# Lights.net
KiCad netlist of a schematic drawn in Altium Designer
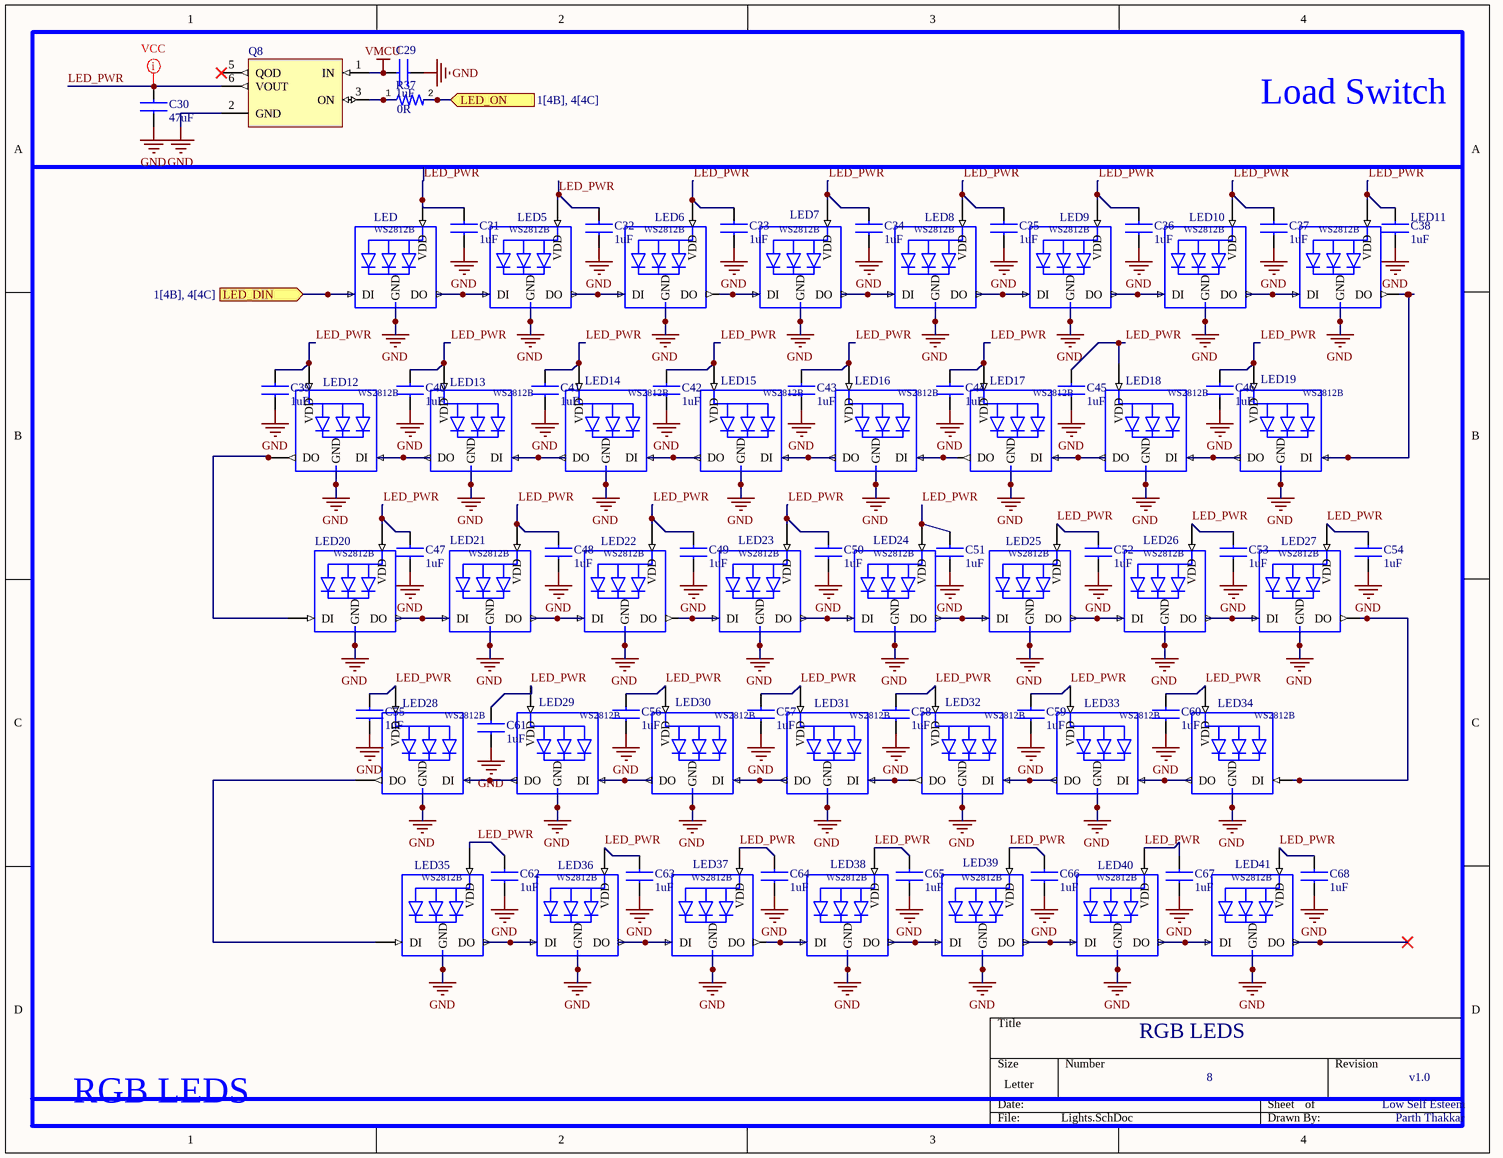
[diagram p0:  Lights.SchDoc]

(export (version "E")
  (design (tool "Eeschema 10.0.6"))
  (components
    (comp (ref "C29")
      (value "1uF")
      (footprint "Capacitor 0603")
      (fields
        (field (name "MANUFACTURER") "Murata")
        (field (name "MANUFACTURER PART NUMBER") "GRM188R61A105KA61D")
        (field (name "Comment") "CAP 1uF 10V 0603")
      )
      (libsource (lib "Keyboard_parts") (part "CAP 1uF 10V 0603"))
    )
    (comp (ref "C30")
      (value "47uF")
      (footprint "CAPACITOR 0805")
      (description "Multilayer Ceramic Capacitors MLCC - SMD/SMT 0805 47uF 10volts *Derate Voltage/Temp")
      (fields
        (field (name "MANUFACTURER") "Murata")
        (field (name "MANUFACTURER PART NUMBER") "GRM21BR61A476ME15K")
      )
      (libsource (lib "Keyboard_parts") (part "CAP 47uF 10V 0805"))
    )
    (comp (ref "C31")
      (value "1uF")
      (footprint "Capacitor 0603")
      (fields
        (field (name "MANUFACTURER") "Murata")
        (field (name "MANUFACTURER PART NUMBER") "GRM188R61A105KA61D")
        (field (name "Comment") "CAP 1uF 10V 0603")
      )
      (libsource (lib "Keyboard_parts") (part "CAP 1uF 10V 0603"))
    )
    (comp (ref "C32")
      (value "1uF")
      (footprint "Capacitor 0603")
      (fields
        (field (name "MANUFACTURER") "Murata")
        (field (name "MANUFACTURER PART NUMBER") "GRM188R61A105KA61D")
        (field (name "Comment") "CAP 1uF 10V 0603")
      )
      (libsource (lib "Keyboard_parts") (part "CAP 1uF 10V 0603"))
    )
    (comp (ref "C33")
      (value "1uF")
      (footprint "Capacitor 0603")
      (fields
        (field (name "MANUFACTURER") "Murata")
        (field (name "MANUFACTURER PART NUMBER") "GRM188R61A105KA61D")
        (field (name "Comment") "CAP 1uF 10V 0603")
      )
      (libsource (lib "Keyboard_parts") (part "CAP 1uF 10V 0603"))
    )
    (comp (ref "C34")
      (value "1uF")
      (footprint "Capacitor 0603")
      (fields
        (field (name "MANUFACTURER") "Murata")
        (field (name "MANUFACTURER PART NUMBER") "GRM188R61A105KA61D")
        (field (name "Comment") "CAP 1uF 10V 0603")
      )
      (libsource (lib "Keyboard_parts") (part "CAP 1uF 10V 0603"))
    )
    (comp (ref "C35")
      (value "1uF")
      (footprint "Capacitor 0603")
      (fields
        (field (name "MANUFACTURER") "Murata")
        (field (name "MANUFACTURER PART NUMBER") "GRM188R61A105KA61D")
        (field (name "Comment") "CAP 1uF 10V 0603")
      )
      (libsource (lib "Keyboard_parts") (part "CAP 1uF 10V 0603"))
    )
    (comp (ref "C36")
      (value "1uF")
      (footprint "Capacitor 0603")
      (fields
        (field (name "MANUFACTURER") "Murata")
        (field (name "MANUFACTURER PART NUMBER") "GRM188R61A105KA61D")
        (field (name "Comment") "CAP 1uF 10V 0603")
      )
      (libsource (lib "Keyboard_parts") (part "CAP 1uF 10V 0603"))
    )
    (comp (ref "C37")
      (value "1uF")
      (footprint "Capacitor 0603")
      (fields
        (field (name "MANUFACTURER") "Murata")
        (field (name "MANUFACTURER PART NUMBER") "GRM188R61A105KA61D")
        (field (name "Comment") "CAP 1uF 10V 0603")
      )
      (libsource (lib "Keyboard_parts") (part "CAP 1uF 10V 0603"))
    )
    (comp (ref "C38")
      (value "1uF")
      (footprint "Capacitor 0603")
      (fields
        (field (name "MANUFACTURER") "Murata")
        (field (name "MANUFACTURER PART NUMBER") "GRM188R61A105KA61D")
        (field (name "Comment") "CAP 1uF 10V 0603")
      )
      (libsource (lib "Keyboard_parts") (part "CAP 1uF 10V 0603"))
    )
    (comp (ref "C39")
      (value "1uF")
      (footprint "Capacitor 0603")
      (fields
        (field (name "MANUFACTURER") "Murata")
        (field (name "MANUFACTURER PART NUMBER") "GRM188R61A105KA61D")
        (field (name "Comment") "CAP 1uF 10V 0603")
      )
      (libsource (lib "Keyboard_parts") (part "CAP 1uF 10V 0603"))
    )
    (comp (ref "C40")
      (value "1uF")
      (footprint "Capacitor 0603")
      (fields
        (field (name "MANUFACTURER") "Murata")
        (field (name "MANUFACTURER PART NUMBER") "GRM188R61A105KA61D")
        (field (name "Comment") "CAP 1uF 10V 0603")
      )
      (libsource (lib "Keyboard_parts") (part "CAP 1uF 10V 0603"))
    )
    (comp (ref "C41")
      (value "1uF")
      (footprint "Capacitor 0603")
      (fields
        (field (name "MANUFACTURER") "Murata")
        (field (name "MANUFACTURER PART NUMBER") "GRM188R61A105KA61D")
        (field (name "Comment") "CAP 1uF 10V 0603")
      )
      (libsource (lib "Keyboard_parts") (part "CAP 1uF 10V 0603"))
    )
    (comp (ref "C42")
      (value "1uF")
      (footprint "Capacitor 0603")
      (fields
        (field (name "MANUFACTURER") "Murata")
        (field (name "MANUFACTURER PART NUMBER") "GRM188R61A105KA61D")
        (field (name "Comment") "CAP 1uF 10V 0603")
      )
      (libsource (lib "Keyboard_parts") (part "CAP 1uF 10V 0603"))
    )
    (comp (ref "C43")
      (value "1uF")
      (footprint "Capacitor 0603")
      (fields
        (field (name "MANUFACTURER") "Murata")
        (field (name "MANUFACTURER PART NUMBER") "GRM188R61A105KA61D")
        (field (name "Comment") "CAP 1uF 10V 0603")
      )
      (libsource (lib "Keyboard_parts") (part "CAP 1uF 10V 0603"))
    )
    (comp (ref "C44")
      (value "1uF")
      (footprint "Capacitor 0603")
      (fields
        (field (name "MANUFACTURER") "Murata")
        (field (name "MANUFACTURER PART NUMBER") "GRM188R61A105KA61D")
        (field (name "Comment") "CAP 1uF 10V 0603")
      )
      (libsource (lib "Keyboard_parts") (part "CAP 1uF 10V 0603"))
    )
    (comp (ref "C45")
      (value "1uF")
      (footprint "Capacitor 0603")
      (fields
        (field (name "MANUFACTURER") "Murata")
        (field (name "MANUFACTURER PART NUMBER") "GRM188R61A105KA61D")
        (field (name "Comment") "CAP 1uF 10V 0603")
      )
      (libsource (lib "Keyboard_parts") (part "CAP 1uF 10V 0603"))
    )
    (comp (ref "C46")
      (value "1uF")
      (footprint "Capacitor 0603")
      (fields
        (field (name "MANUFACTURER") "Murata")
        (field (name "MANUFACTURER PART NUMBER") "GRM188R61A105KA61D")
        (field (name "Comment") "CAP 1uF 10V 0603")
      )
      (libsource (lib "Keyboard_parts") (part "CAP 1uF 10V 0603"))
    )
    (comp (ref "C47")
      (value "1uF")
      (footprint "Capacitor 0603")
      (fields
        (field (name "MANUFACTURER") "Murata")
        (field (name "MANUFACTURER PART NUMBER") "GRM188R61A105KA61D")
        (field (name "Comment") "CAP 1uF 10V 0603")
      )
      (libsource (lib "Keyboard_parts") (part "CAP 1uF 10V 0603"))
    )
    (comp (ref "C48")
      (value "1uF")
      (footprint "Capacitor 0603")
      (fields
        (field (name "MANUFACTURER") "Murata")
        (field (name "MANUFACTURER PART NUMBER") "GRM188R61A105KA61D")
        (field (name "Comment") "CAP 1uF 10V 0603")
      )
      (libsource (lib "Keyboard_parts") (part "CAP 1uF 10V 0603"))
    )
    (comp (ref "C49")
      (value "1uF")
      (footprint "Capacitor 0603")
      (fields
        (field (name "MANUFACTURER") "Murata")
        (field (name "MANUFACTURER PART NUMBER") "GRM188R61A105KA61D")
        (field (name "Comment") "CAP 1uF 10V 0603")
      )
      (libsource (lib "Keyboard_parts") (part "CAP 1uF 10V 0603"))
    )
    (comp (ref "C50")
      (value "1uF")
      (footprint "Capacitor 0603")
      (fields
        (field (name "MANUFACTURER") "Murata")
        (field (name "MANUFACTURER PART NUMBER") "GRM188R61A105KA61D")
        (field (name "Comment") "CAP 1uF 10V 0603")
      )
      (libsource (lib "Keyboard_parts") (part "CAP 1uF 10V 0603"))
    )
    (comp (ref "C51")
      (value "1uF")
      (footprint "Capacitor 0603")
      (fields
        (field (name "MANUFACTURER") "Murata")
        (field (name "MANUFACTURER PART NUMBER") "GRM188R61A105KA61D")
        (field (name "Comment") "CAP 1uF 10V 0603")
      )
      (libsource (lib "Keyboard_parts") (part "CAP 1uF 10V 0603"))
    )
    (comp (ref "C52")
      (value "1uF")
      (footprint "Capacitor 0603")
      (fields
        (field (name "MANUFACTURER") "Murata")
        (field (name "MANUFACTURER PART NUMBER") "GRM188R61A105KA61D")
        (field (name "Comment") "CAP 1uF 10V 0603")
      )
      (libsource (lib "Keyboard_parts") (part "CAP 1uF 10V 0603"))
    )
    (comp (ref "C53")
      (value "1uF")
      (footprint "Capacitor 0603")
      (fields
        (field (name "MANUFACTURER") "Murata")
        (field (name "MANUFACTURER PART NUMBER") "GRM188R61A105KA61D")
        (field (name "Comment") "CAP 1uF 10V 0603")
      )
      (libsource (lib "Keyboard_parts") (part "CAP 1uF 10V 0603"))
    )
    (comp (ref "C54")
      (value "1uF")
      (footprint "Capacitor 0603")
      (fields
        (field (name "MANUFACTURER") "Murata")
        (field (name "MANUFACTURER PART NUMBER") "GRM188R61A105KA61D")
        (field (name "Comment") "CAP 1uF 10V 0603")
      )
      (libsource (lib "Keyboard_parts") (part "CAP 1uF 10V 0603"))
    )
    (comp (ref "C55")
      (value "1uF")
      (footprint "Capacitor 0603")
      (fields
        (field (name "MANUFACTURER") "Murata")
        (field (name "MANUFACTURER PART NUMBER") "GRM188R61A105KA61D")
        (field (name "Comment") "CAP 1uF 10V 0603")
      )
      (libsource (lib "Keyboard_parts") (part "CAP 1uF 10V 0603"))
    )
    (comp (ref "C56")
      (value "1uF")
      (footprint "Capacitor 0603")
      (fields
        (field (name "MANUFACTURER") "Murata")
        (field (name "MANUFACTURER PART NUMBER") "GRM188R61A105KA61D")
        (field (name "Comment") "CAP 1uF 10V 0603")
      )
      (libsource (lib "Keyboard_parts") (part "CAP 1uF 10V 0603"))
    )
    (comp (ref "C57")
      (value "1uF")
      (footprint "Capacitor 0603")
      (fields
        (field (name "MANUFACTURER") "Murata")
        (field (name "MANUFACTURER PART NUMBER") "GRM188R61A105KA61D")
        (field (name "Comment") "CAP 1uF 10V 0603")
      )
      (libsource (lib "Keyboard_parts") (part "CAP 1uF 10V 0603"))
    )
    (comp (ref "C58")
      (value "1uF")
      (footprint "Capacitor 0603")
      (fields
        (field (name "MANUFACTURER") "Murata")
        (field (name "MANUFACTURER PART NUMBER") "GRM188R61A105KA61D")
        (field (name "Comment") "CAP 1uF 10V 0603")
      )
      (libsource (lib "Keyboard_parts") (part "CAP 1uF 10V 0603"))
    )
    (comp (ref "C59")
      (value "1uF")
      (footprint "Capacitor 0603")
      (fields
        (field (name "MANUFACTURER") "Murata")
        (field (name "MANUFACTURER PART NUMBER") "GRM188R61A105KA61D")
        (field (name "Comment") "CAP 1uF 10V 0603")
      )
      (libsource (lib "Keyboard_parts") (part "CAP 1uF 10V 0603"))
    )
    (comp (ref "C60")
      (value "1uF")
      (footprint "Capacitor 0603")
      (fields
        (field (name "MANUFACTURER") "Murata")
        (field (name "MANUFACTURER PART NUMBER") "GRM188R61A105KA61D")
        (field (name "Comment") "CAP 1uF 10V 0603")
      )
      (libsource (lib "Keyboard_parts") (part "CAP 1uF 10V 0603"))
    )
    (comp (ref "C61")
      (value "1uF")
      (footprint "Capacitor 0603")
      (fields
        (field (name "MANUFACTURER") "Murata")
        (field (name "MANUFACTURER PART NUMBER") "GRM188R61A105KA61D")
        (field (name "Comment") "CAP 1uF 10V 0603")
      )
      (libsource (lib "Keyboard_parts") (part "CAP 1uF 10V 0603"))
    )
    (comp (ref "C62")
      (value "1uF")
      (footprint "Capacitor 0603")
      (fields
        (field (name "MANUFACTURER") "Murata")
        (field (name "MANUFACTURER PART NUMBER") "GRM188R61A105KA61D")
        (field (name "Comment") "CAP 1uF 10V 0603")
      )
      (libsource (lib "Keyboard_parts") (part "CAP 1uF 10V 0603"))
    )
    (comp (ref "C63")
      (value "1uF")
      (footprint "Capacitor 0603")
      (fields
        (field (name "MANUFACTURER") "Murata")
        (field (name "MANUFACTURER PART NUMBER") "GRM188R61A105KA61D")
        (field (name "Comment") "CAP 1uF 10V 0603")
      )
      (libsource (lib "Keyboard_parts") (part "CAP 1uF 10V 0603"))
    )
    (comp (ref "C64")
      (value "1uF")
      (footprint "Capacitor 0603")
      (fields
        (field (name "MANUFACTURER") "Murata")
        (field (name "MANUFACTURER PART NUMBER") "GRM188R61A105KA61D")
        (field (name "Comment") "CAP 1uF 10V 0603")
      )
      (libsource (lib "Keyboard_parts") (part "CAP 1uF 10V 0603"))
    )
    (comp (ref "C65")
      (value "1uF")
      (footprint "Capacitor 0603")
      (fields
        (field (name "MANUFACTURER") "Murata")
        (field (name "MANUFACTURER PART NUMBER") "GRM188R61A105KA61D")
        (field (name "Comment") "CAP 1uF 10V 0603")
      )
      (libsource (lib "Keyboard_parts") (part "CAP 1uF 10V 0603"))
    )
    (comp (ref "C66")
      (value "1uF")
      (footprint "Capacitor 0603")
      (fields
        (field (name "MANUFACTURER") "Murata")
        (field (name "MANUFACTURER PART NUMBER") "GRM188R61A105KA61D")
        (field (name "Comment") "CAP 1uF 10V 0603")
      )
      (libsource (lib "Keyboard_parts") (part "CAP 1uF 10V 0603"))
    )
    (comp (ref "C67")
      (value "1uF")
      (footprint "Capacitor 0603")
      (fields
        (field (name "MANUFACTURER") "Murata")
        (field (name "MANUFACTURER PART NUMBER") "GRM188R61A105KA61D")
        (field (name "Comment") "CAP 1uF 10V 0603")
      )
      (libsource (lib "Keyboard_parts") (part "CAP 1uF 10V 0603"))
    )
    (comp (ref "C68")
      (value "1uF")
      (footprint "Capacitor 0603")
      (fields
        (field (name "MANUFACTURER") "Murata")
        (field (name "MANUFACTURER PART NUMBER") "GRM188R61A105KA61D")
        (field (name "Comment") "CAP 1uF 10V 0603")
      )
      (libsource (lib "Keyboard_parts") (part "CAP 1uF 10V 0603"))
    )
    (comp (ref "LED")
      (value "WS2812B")
      (footprint "WS2812B")
      (description "Raspberry Pi HAT _40 pin_ Wheeled Robotics Kit")
      (fields (field (name "MF") "SparkFun Electronics"))
      (libsource (lib "Keyboard_parts") (part "WS2812B"))
    )
    (comp (ref "LED5")
      (value "WS2812B")
      (footprint "WS2812B")
      (description "Raspberry Pi HAT _40 pin_ Wheeled Robotics Kit")
      (fields (field (name "MF") "SparkFun Electronics"))
      (libsource (lib "Keyboard_parts") (part "WS2812B"))
    )
    (comp (ref "LED6")
      (value "WS2812B")
      (footprint "WS2812B")
      (description "Raspberry Pi HAT _40 pin_ Wheeled Robotics Kit")
      (fields (field (name "MF") "SparkFun Electronics"))
      (libsource (lib "Keyboard_parts") (part "WS2812B"))
    )
    (comp (ref "LED7")
      (value "WS2812B")
      (footprint "WS2812B")
      (description "Raspberry Pi HAT _40 pin_ Wheeled Robotics Kit")
      (fields (field (name "MF") "SparkFun Electronics"))
      (libsource (lib "Keyboard_parts") (part "WS2812B"))
    )
    (comp (ref "LED8")
      (value "WS2812B")
      (footprint "WS2812B")
      (description "Raspberry Pi HAT _40 pin_ Wheeled Robotics Kit")
      (fields (field (name "MF") "SparkFun Electronics"))
      (libsource (lib "Keyboard_parts") (part "WS2812B"))
    )
    (comp (ref "LED9")
      (value "WS2812B")
      (footprint "WS2812B")
      (description "Raspberry Pi HAT _40 pin_ Wheeled Robotics Kit")
      (fields (field (name "MF") "SparkFun Electronics"))
      (libsource (lib "Keyboard_parts") (part "WS2812B"))
    )
    (comp (ref "LED10")
      (value "WS2812B")
      (footprint "WS2812B")
      (description "Raspberry Pi HAT _40 pin_ Wheeled Robotics Kit")
      (fields (field (name "MF") "SparkFun Electronics"))
      (libsource (lib "Keyboard_parts") (part "WS2812B"))
    )
    (comp (ref "LED11")
      (value "WS2812B")
      (footprint "WS2812B")
      (description "Raspberry Pi HAT _40 pin_ Wheeled Robotics Kit")
      (fields (field (name "MF") "SparkFun Electronics"))
      (libsource (lib "Keyboard_parts") (part "WS2812B"))
    )
    (comp (ref "LED12")
      (value "WS2812B")
      (footprint "WS2812B")
      (description "Raspberry Pi HAT _40 pin_ Wheeled Robotics Kit")
      (fields (field (name "MF") "SparkFun Electronics"))
      (libsource (lib "Keyboard_parts") (part "WS2812B"))
    )
    (comp (ref "LED13")
      (value "WS2812B")
      (footprint "WS2812B")
      (description "Raspberry Pi HAT _40 pin_ Wheeled Robotics Kit")
      (fields (field (name "MF") "SparkFun Electronics"))
      (libsource (lib "Keyboard_parts") (part "WS2812B"))
    )
    (comp (ref "LED14")
      (value "WS2812B")
      (footprint "WS2812B")
      (description "Raspberry Pi HAT _40 pin_ Wheeled Robotics Kit")
      (fields (field (name "MF") "SparkFun Electronics"))
      (libsource (lib "Keyboard_parts") (part "WS2812B"))
    )
    (comp (ref "LED15")
      (value "WS2812B")
      (footprint "WS2812B")
      (description "Raspberry Pi HAT _40 pin_ Wheeled Robotics Kit")
      (fields (field (name "MF") "SparkFun Electronics"))
      (libsource (lib "Keyboard_parts") (part "WS2812B"))
    )
    (comp (ref "LED16")
      (value "WS2812B")
      (footprint "WS2812B")
      (description "Raspberry Pi HAT _40 pin_ Wheeled Robotics Kit")
      (fields (field (name "MF") "SparkFun Electronics"))
      (libsource (lib "Keyboard_parts") (part "WS2812B"))
    )
    (comp (ref "LED17")
      (value "WS2812B")
      (footprint "WS2812B")
      (description "Raspberry Pi HAT _40 pin_ Wheeled Robotics Kit")
      (fields (field (name "MF") "SparkFun Electronics"))
      (libsource (lib "Keyboard_parts") (part "WS2812B"))
    )
    (comp (ref "LED18")
      (value "WS2812B")
      (footprint "WS2812B")
      (description "Raspberry Pi HAT _40 pin_ Wheeled Robotics Kit")
      (fields (field (name "MF") "SparkFun Electronics"))
      (libsource (lib "Keyboard_parts") (part "WS2812B"))
    )
    (comp (ref "LED19")
      (value "WS2812B")
      (footprint "WS2812B")
      (description "Raspberry Pi HAT _40 pin_ Wheeled Robotics Kit")
      (fields (field (name "MF") "SparkFun Electronics"))
      (libsource (lib "Keyboard_parts") (part "WS2812B"))
    )
    (comp (ref "LED20")
      (value "WS2812B")
      (footprint "WS2812B")
      (description "Raspberry Pi HAT _40 pin_ Wheeled Robotics Kit")
      (fields (field (name "MF") "SparkFun Electronics"))
      (libsource (lib "Keyboard_parts") (part "WS2812B"))
    )
    (comp (ref "LED21")
      (value "WS2812B")
      (footprint "WS2812B")
      (description "Raspberry Pi HAT _40 pin_ Wheeled Robotics Kit")
      (fields (field (name "MF") "SparkFun Electronics"))
      (libsource (lib "Keyboard_parts") (part "WS2812B"))
    )
    (comp (ref "LED22")
      (value "WS2812B")
      (footprint "WS2812B")
      (description "Raspberry Pi HAT _40 pin_ Wheeled Robotics Kit")
      (fields (field (name "MF") "SparkFun Electronics"))
      (libsource (lib "Keyboard_parts") (part "WS2812B"))
    )
    (comp (ref "LED23")
      (value "WS2812B")
      (footprint "WS2812B")
      (description "Raspberry Pi HAT _40 pin_ Wheeled Robotics Kit")
      (fields (field (name "MF") "SparkFun Electronics"))
      (libsource (lib "Keyboard_parts") (part "WS2812B"))
    )
    (comp (ref "LED24")
      (value "WS2812B")
      (footprint "WS2812B")
      (description "Raspberry Pi HAT _40 pin_ Wheeled Robotics Kit")
      (fields (field (name "MF") "SparkFun Electronics"))
      (libsource (lib "Keyboard_parts") (part "WS2812B"))
    )
    (comp (ref "LED25")
      (value "WS2812B")
      (footprint "WS2812B")
      (description "Raspberry Pi HAT _40 pin_ Wheeled Robotics Kit")
      (fields (field (name "MF") "SparkFun Electronics"))
      (libsource (lib "Keyboard_parts") (part "WS2812B"))
    )
    (comp (ref "LED26")
      (value "WS2812B")
      (footprint "WS2812B")
      (description "Raspberry Pi HAT _40 pin_ Wheeled Robotics Kit")
      (fields (field (name "MF") "SparkFun Electronics"))
      (libsource (lib "Keyboard_parts") (part "WS2812B"))
    )
    (comp (ref "LED27")
      (value "WS2812B")
      (footprint "WS2812B")
      (description "Raspberry Pi HAT _40 pin_ Wheeled Robotics Kit")
      (fields (field (name "MF") "SparkFun Electronics"))
      (libsource (lib "Keyboard_parts") (part "WS2812B"))
    )
    (comp (ref "LED28")
      (value "WS2812B")
      (footprint "WS2812B")
      (description "Raspberry Pi HAT _40 pin_ Wheeled Robotics Kit")
      (fields (field (name "MF") "SparkFun Electronics"))
      (libsource (lib "Keyboard_parts") (part "WS2812B"))
    )
    (comp (ref "LED29")
      (value "WS2812B")
      (footprint "WS2812B")
      (description "Raspberry Pi HAT _40 pin_ Wheeled Robotics Kit")
      (fields (field (name "MF") "SparkFun Electronics"))
      (libsource (lib "Keyboard_parts") (part "WS2812B"))
    )
    (comp (ref "LED30")
      (value "WS2812B")
      (footprint "WS2812B")
      (description "Raspberry Pi HAT _40 pin_ Wheeled Robotics Kit")
      (fields (field (name "MF") "SparkFun Electronics"))
      (libsource (lib "Keyboard_parts") (part "WS2812B"))
    )
    (comp (ref "LED31")
      (value "WS2812B")
      (footprint "WS2812B")
      (description "Raspberry Pi HAT _40 pin_ Wheeled Robotics Kit")
      (fields (field (name "MF") "SparkFun Electronics"))
      (libsource (lib "Keyboard_parts") (part "WS2812B"))
    )
    (comp (ref "LED32")
      (value "WS2812B")
      (footprint "WS2812B")
      (description "Raspberry Pi HAT _40 pin_ Wheeled Robotics Kit")
      (fields (field (name "MF") "SparkFun Electronics"))
      (libsource (lib "Keyboard_parts") (part "WS2812B"))
    )
    (comp (ref "LED33")
      (value "WS2812B")
      (footprint "WS2812B")
      (description "Raspberry Pi HAT _40 pin_ Wheeled Robotics Kit")
      (fields (field (name "MF") "SparkFun Electronics"))
      (libsource (lib "Keyboard_parts") (part "WS2812B"))
    )
    (comp (ref "LED34")
      (value "WS2812B")
      (footprint "WS2812B")
      (description "Raspberry Pi HAT _40 pin_ Wheeled Robotics Kit")
      (fields (field (name "MF") "SparkFun Electronics"))
      (libsource (lib "Keyboard_parts") (part "WS2812B"))
    )
    (comp (ref "LED35")
      (value "WS2812B")
      (footprint "WS2812B")
      (description "Raspberry Pi HAT _40 pin_ Wheeled Robotics Kit")
      (fields (field (name "MF") "SparkFun Electronics"))
      (libsource (lib "Keyboard_parts") (part "WS2812B"))
    )
    (comp (ref "LED36")
      (value "WS2812B")
      (footprint "WS2812B")
      (description "Raspberry Pi HAT _40 pin_ Wheeled Robotics Kit")
      (fields (field (name "MF") "SparkFun Electronics"))
      (libsource (lib "Keyboard_parts") (part "WS2812B"))
    )
    (comp (ref "LED37")
      (value "WS2812B")
      (footprint "WS2812B")
      (description "Raspberry Pi HAT _40 pin_ Wheeled Robotics Kit")
      (fields (field (name "MF") "SparkFun Electronics"))
      (libsource (lib "Keyboard_parts") (part "WS2812B"))
    )
    (comp (ref "LED38")
      (value "WS2812B")
      (footprint "WS2812B")
      (description "Raspberry Pi HAT _40 pin_ Wheeled Robotics Kit")
      (fields (field (name "MF") "SparkFun Electronics"))
      (libsource (lib "Keyboard_parts") (part "WS2812B"))
    )
    (comp (ref "LED39")
      (value "WS2812B")
      (footprint "WS2812B")
      (description "Raspberry Pi HAT _40 pin_ Wheeled Robotics Kit")
      (fields (field (name "MF") "SparkFun Electronics"))
      (libsource (lib "Keyboard_parts") (part "WS2812B"))
    )
    (comp (ref "LED40")
      (value "WS2812B")
      (footprint "WS2812B")
      (description "Raspberry Pi HAT _40 pin_ Wheeled Robotics Kit")
      (fields (field (name "MF") "SparkFun Electronics"))
      (libsource (lib "Keyboard_parts") (part "WS2812B"))
    )
    (comp (ref "LED41")
      (value "WS2812B")
      (footprint "WS2812B")
      (description "Raspberry Pi HAT _40 pin_ Wheeled Robotics Kit")
      (fields (field (name "MF") "SparkFun Electronics"))
      (libsource (lib "Keyboard_parts") (part "WS2812B"))
    )
    (comp (ref "Q8")
      (value "TPS22919")
      (footprint "TPS22919DCKR - Load SW")
      (description "Buffer/Inverter Based Peripheral Driver, 3A, PDSO6")
      (fields
        (field (name "MANUFACTURER") "Texas Instruments")
        (field (name "MANUFACTURER PART NUMBER") "TPS22919DCKT")
      )
      (libsource (lib "Keyboard_parts") (part "TPS22919"))
    )
    (comp (ref "R37")
      (value "0R")
      (footprint "Resistor 0402")
      (description "Metal Glaze/thick Film, 0.0625W, 0ohm, Surface Mount, 0402")
      (fields
        (field (name "MANUFACTURER") "Yageo")
        (field (name "MANUFACTURER PART NUMBER") "RC0402JR-070RL")
      )
      (libsource (lib "InsaneIntegratedLib") (part "RES 0R 0402"))
    )
  )
  (nets
    (net (code "2") (name "/LED_DIN") (class "Default")
      (node (ref "LED") (pin "4-DIN") (pinfunction "DI_4-DIN") (pintype "input"))
    )
    (net (code "3") (name "/LED_ON") (class "Default")
      (node (ref "R37") (pin "2") (pinfunction "2_2") (pintype "passive"))
    )
    (net (code "4") (name "/LED_PWR") (class "Default")
      (node (ref "C30") (pin "1") (pinfunction "1_1") (pintype "passive"))
      (node (ref "C31") (pin "1") (pinfunction "1_1") (pintype "passive"))
      (node (ref "C32") (pin "1") (pinfunction "1_1") (pintype "passive"))
      (node (ref "C33") (pin "1") (pinfunction "1_1") (pintype "passive"))
      (node (ref "C34") (pin "1") (pinfunction "1_1") (pintype "passive"))
      (node (ref "C35") (pin "1") (pinfunction "1_1") (pintype "passive"))
      (node (ref "C36") (pin "1") (pinfunction "1_1") (pintype "passive"))
      (node (ref "C37") (pin "1") (pinfunction "1_1") (pintype "passive"))
      (node (ref "C38") (pin "1") (pinfunction "1_1") (pintype "passive"))
      (node (ref "C39") (pin "1") (pinfunction "1_1") (pintype "passive"))
      (node (ref "C40") (pin "1") (pinfunction "1_1") (pintype "passive"))
      (node (ref "C41") (pin "1") (pinfunction "1_1") (pintype "passive"))
      (node (ref "C42") (pin "1") (pinfunction "1_1") (pintype "passive"))
      (node (ref "C43") (pin "1") (pinfunction "1_1") (pintype "passive"))
      (node (ref "C44") (pin "1") (pinfunction "1_1") (pintype "passive"))
      (node (ref "C45") (pin "1") (pinfunction "1_1") (pintype "passive"))
      (node (ref "C46") (pin "1") (pinfunction "1_1") (pintype "passive"))
      (node (ref "C47") (pin "1") (pinfunction "1_1") (pintype "passive"))
      (node (ref "C48") (pin "1") (pinfunction "1_1") (pintype "passive"))
      (node (ref "C49") (pin "1") (pinfunction "1_1") (pintype "passive"))
      (node (ref "C50") (pin "1") (pinfunction "1_1") (pintype "passive"))
      (node (ref "C51") (pin "1") (pinfunction "1_1") (pintype "passive"))
      (node (ref "C52") (pin "1") (pinfunction "1_1") (pintype "passive"))
      (node (ref "C53") (pin "1") (pinfunction "1_1") (pintype "passive"))
      (node (ref "C54") (pin "1") (pinfunction "1_1") (pintype "passive"))
      (node (ref "C55") (pin "1") (pinfunction "1_1") (pintype "passive"))
      (node (ref "C56") (pin "1") (pinfunction "1_1") (pintype "passive"))
      (node (ref "C57") (pin "1") (pinfunction "1_1") (pintype "passive"))
      (node (ref "C58") (pin "1") (pinfunction "1_1") (pintype "passive"))
      (node (ref "C59") (pin "1") (pinfunction "1_1") (pintype "passive"))
      (node (ref "C60") (pin "1") (pinfunction "1_1") (pintype "passive"))
      (node (ref "C61") (pin "1") (pinfunction "1_1") (pintype "passive"))
      (node (ref "C62") (pin "1") (pinfunction "1_1") (pintype "passive"))
      (node (ref "C63") (pin "1") (pinfunction "1_1") (pintype "passive"))
      (node (ref "C64") (pin "1") (pinfunction "1_1") (pintype "passive"))
      (node (ref "C65") (pin "1") (pinfunction "1_1") (pintype "passive"))
      (node (ref "C66") (pin "1") (pinfunction "1_1") (pintype "passive"))
      (node (ref "C67") (pin "1") (pinfunction "1_1") (pintype "passive"))
      (node (ref "C68") (pin "1") (pinfunction "1_1") (pintype "passive"))
      (node (ref "LED") (pin "1-VDD") (pinfunction "VDD_1-VDD") (pintype "input"))
      (node (ref "LED10") (pin "1-VDD") (pinfunction "VDD_1-VDD") (pintype "input"))
      (node (ref "LED11") (pin "1-VDD") (pinfunction "VDD_1-VDD") (pintype "input"))
      (node (ref "LED12") (pin "1-VDD") (pinfunction "VDD_1-VDD") (pintype "input"))
      (node (ref "LED13") (pin "1-VDD") (pinfunction "VDD_1-VDD") (pintype "input"))
      (node (ref "LED14") (pin "1-VDD") (pinfunction "VDD_1-VDD") (pintype "input"))
      (node (ref "LED15") (pin "1-VDD") (pinfunction "VDD_1-VDD") (pintype "input"))
      (node (ref "LED16") (pin "1-VDD") (pinfunction "VDD_1-VDD") (pintype "input"))
      (node (ref "LED17") (pin "1-VDD") (pinfunction "VDD_1-VDD") (pintype "input"))
      (node (ref "LED18") (pin "1-VDD") (pinfunction "VDD_1-VDD") (pintype "input"))
      (node (ref "LED19") (pin "1-VDD") (pinfunction "VDD_1-VDD") (pintype "input"))
      (node (ref "LED20") (pin "1-VDD") (pinfunction "VDD_1-VDD") (pintype "input"))
      (node (ref "LED21") (pin "1-VDD") (pinfunction "VDD_1-VDD") (pintype "input"))
      (node (ref "LED22") (pin "1-VDD") (pinfunction "VDD_1-VDD") (pintype "input"))
      (node (ref "LED23") (pin "1-VDD") (pinfunction "VDD_1-VDD") (pintype "input"))
      (node (ref "LED24") (pin "1-VDD") (pinfunction "VDD_1-VDD") (pintype "input"))
      (node (ref "LED25") (pin "1-VDD") (pinfunction "VDD_1-VDD") (pintype "input"))
      (node (ref "LED26") (pin "1-VDD") (pinfunction "VDD_1-VDD") (pintype "input"))
      (node (ref "LED27") (pin "1-VDD") (pinfunction "VDD_1-VDD") (pintype "input"))
      (node (ref "LED28") (pin "1-VDD") (pinfunction "VDD_1-VDD") (pintype "input"))
      (node (ref "LED29") (pin "1-VDD") (pinfunction "VDD_1-VDD") (pintype "input"))
      (node (ref "LED30") (pin "1-VDD") (pinfunction "VDD_1-VDD") (pintype "input"))
      (node (ref "LED31") (pin "1-VDD") (pinfunction "VDD_1-VDD") (pintype "input"))
      (node (ref "LED32") (pin "1-VDD") (pinfunction "VDD_1-VDD") (pintype "input"))
      (node (ref "LED33") (pin "1-VDD") (pinfunction "VDD_1-VDD") (pintype "input"))
      (node (ref "LED34") (pin "1-VDD") (pinfunction "VDD_1-VDD") (pintype "input"))
      (node (ref "LED35") (pin "1-VDD") (pinfunction "VDD_1-VDD") (pintype "input"))
      (node (ref "LED36") (pin "1-VDD") (pinfunction "VDD_1-VDD") (pintype "input"))
      (node (ref "LED37") (pin "1-VDD") (pinfunction "VDD_1-VDD") (pintype "input"))
      (node (ref "LED38") (pin "1-VDD") (pinfunction "VDD_1-VDD") (pintype "input"))
      (node (ref "LED39") (pin "1-VDD") (pinfunction "VDD_1-VDD") (pintype "input"))
      (node (ref "LED40") (pin "1-VDD") (pinfunction "VDD_1-VDD") (pintype "input"))
      (node (ref "LED41") (pin "1-VDD") (pinfunction "VDD_1-VDD") (pintype "input"))
      (node (ref "LED5") (pin "1-VDD") (pinfunction "VDD_1-VDD") (pintype "input"))
      (node (ref "LED6") (pin "1-VDD") (pinfunction "VDD_1-VDD") (pintype "input"))
      (node (ref "LED7") (pin "1-VDD") (pinfunction "VDD_1-VDD") (pintype "input"))
      (node (ref "LED8") (pin "1-VDD") (pinfunction "VDD_1-VDD") (pintype "input"))
      (node (ref "LED9") (pin "1-VDD") (pinfunction "VDD_1-VDD") (pintype "input"))
      (node (ref "Q8") (pin "6") (pinfunction "VOUT_6") (pintype "output"))
    )
    (net (code "5") (name "GND") (class "Default")
      (node (ref "C29") (pin "2") (pinfunction "2_2") (pintype "passive"))
      (node (ref "C30") (pin "2") (pinfunction "2_2") (pintype "passive"))
      (node (ref "C31") (pin "2") (pinfunction "2_2") (pintype "passive"))
      (node (ref "C32") (pin "2") (pinfunction "2_2") (pintype "passive"))
      (node (ref "C33") (pin "2") (pinfunction "2_2") (pintype "passive"))
      (node (ref "C34") (pin "2") (pinfunction "2_2") (pintype "passive"))
      (node (ref "C35") (pin "2") (pinfunction "2_2") (pintype "passive"))
      (node (ref "C36") (pin "2") (pinfunction "2_2") (pintype "passive"))
      (node (ref "C37") (pin "2") (pinfunction "2_2") (pintype "passive"))
      (node (ref "C38") (pin "2") (pinfunction "2_2") (pintype "passive"))
      (node (ref "C39") (pin "2") (pinfunction "2_2") (pintype "passive"))
      (node (ref "C40") (pin "2") (pinfunction "2_2") (pintype "passive"))
      (node (ref "C41") (pin "2") (pinfunction "2_2") (pintype "passive"))
      (node (ref "C42") (pin "2") (pinfunction "2_2") (pintype "passive"))
      (node (ref "C43") (pin "2") (pinfunction "2_2") (pintype "passive"))
      (node (ref "C44") (pin "2") (pinfunction "2_2") (pintype "passive"))
      (node (ref "C45") (pin "2") (pinfunction "2_2") (pintype "passive"))
      (node (ref "C46") (pin "2") (pinfunction "2_2") (pintype "passive"))
      (node (ref "C47") (pin "2") (pinfunction "2_2") (pintype "passive"))
      (node (ref "C48") (pin "2") (pinfunction "2_2") (pintype "passive"))
      (node (ref "C49") (pin "2") (pinfunction "2_2") (pintype "passive"))
      (node (ref "C50") (pin "2") (pinfunction "2_2") (pintype "passive"))
      (node (ref "C51") (pin "2") (pinfunction "2_2") (pintype "passive"))
      (node (ref "C52") (pin "2") (pinfunction "2_2") (pintype "passive"))
      (node (ref "C53") (pin "2") (pinfunction "2_2") (pintype "passive"))
      (node (ref "C54") (pin "2") (pinfunction "2_2") (pintype "passive"))
      (node (ref "C55") (pin "2") (pinfunction "2_2") (pintype "passive"))
      (node (ref "C56") (pin "2") (pinfunction "2_2") (pintype "passive"))
      (node (ref "C57") (pin "2") (pinfunction "2_2") (pintype "passive"))
      (node (ref "C58") (pin "2") (pinfunction "2_2") (pintype "passive"))
      (node (ref "C59") (pin "2") (pinfunction "2_2") (pintype "passive"))
      (node (ref "C60") (pin "2") (pinfunction "2_2") (pintype "passive"))
      (node (ref "C61") (pin "2") (pinfunction "2_2") (pintype "passive"))
      (node (ref "C62") (pin "2") (pinfunction "2_2") (pintype "passive"))
      (node (ref "C63") (pin "2") (pinfunction "2_2") (pintype "passive"))
      (node (ref "C64") (pin "2") (pinfunction "2_2") (pintype "passive"))
      (node (ref "C65") (pin "2") (pinfunction "2_2") (pintype "passive"))
      (node (ref "C66") (pin "2") (pinfunction "2_2") (pintype "passive"))
      (node (ref "C67") (pin "2") (pinfunction "2_2") (pintype "passive"))
      (node (ref "C68") (pin "2") (pinfunction "2_2") (pintype "passive"))
      (node (ref "LED") (pin "3-GND") (pinfunction "GND_3-GND") (pintype "power_in"))
      (node (ref "LED10") (pin "3-GND") (pinfunction "GND_3-GND") (pintype "power_in"))
      (node (ref "LED11") (pin "3-GND") (pinfunction "GND_3-GND") (pintype "power_in"))
      (node (ref "LED12") (pin "3-GND") (pinfunction "GND_3-GND") (pintype "power_in"))
      (node (ref "LED13") (pin "3-GND") (pinfunction "GND_3-GND") (pintype "power_in"))
      (node (ref "LED14") (pin "3-GND") (pinfunction "GND_3-GND") (pintype "power_in"))
      (node (ref "LED15") (pin "3-GND") (pinfunction "GND_3-GND") (pintype "power_in"))
      (node (ref "LED16") (pin "3-GND") (pinfunction "GND_3-GND") (pintype "power_in"))
      (node (ref "LED17") (pin "3-GND") (pinfunction "GND_3-GND") (pintype "power_in"))
      (node (ref "LED18") (pin "3-GND") (pinfunction "GND_3-GND") (pintype "power_in"))
      (node (ref "LED19") (pin "3-GND") (pinfunction "GND_3-GND") (pintype "power_in"))
      (node (ref "LED20") (pin "3-GND") (pinfunction "GND_3-GND") (pintype "power_in"))
      (node (ref "LED21") (pin "3-GND") (pinfunction "GND_3-GND") (pintype "power_in"))
      (node (ref "LED22") (pin "3-GND") (pinfunction "GND_3-GND") (pintype "power_in"))
      (node (ref "LED23") (pin "3-GND") (pinfunction "GND_3-GND") (pintype "power_in"))
      (node (ref "LED24") (pin "3-GND") (pinfunction "GND_3-GND") (pintype "power_in"))
      (node (ref "LED25") (pin "3-GND") (pinfunction "GND_3-GND") (pintype "power_in"))
      (node (ref "LED26") (pin "3-GND") (pinfunction "GND_3-GND") (pintype "power_in"))
      (node (ref "LED27") (pin "3-GND") (pinfunction "GND_3-GND") (pintype "power_in"))
      (node (ref "LED28") (pin "3-GND") (pinfunction "GND_3-GND") (pintype "power_in"))
      (node (ref "LED29") (pin "3-GND") (pinfunction "GND_3-GND") (pintype "power_in"))
      (node (ref "LED30") (pin "3-GND") (pinfunction "GND_3-GND") (pintype "power_in"))
      (node (ref "LED31") (pin "3-GND") (pinfunction "GND_3-GND") (pintype "power_in"))
      (node (ref "LED32") (pin "3-GND") (pinfunction "GND_3-GND") (pintype "power_in"))
      (node (ref "LED33") (pin "3-GND") (pinfunction "GND_3-GND") (pintype "power_in"))
      (node (ref "LED34") (pin "3-GND") (pinfunction "GND_3-GND") (pintype "power_in"))
      (node (ref "LED35") (pin "3-GND") (pinfunction "GND_3-GND") (pintype "power_in"))
      (node (ref "LED36") (pin "3-GND") (pinfunction "GND_3-GND") (pintype "power_in"))
      (node (ref "LED37") (pin "3-GND") (pinfunction "GND_3-GND") (pintype "power_in"))
      (node (ref "LED38") (pin "3-GND") (pinfunction "GND_3-GND") (pintype "power_in"))
      (node (ref "LED39") (pin "3-GND") (pinfunction "GND_3-GND") (pintype "power_in"))
      (node (ref "LED40") (pin "3-GND") (pinfunction "GND_3-GND") (pintype "power_in"))
      (node (ref "LED41") (pin "3-GND") (pinfunction "GND_3-GND") (pintype "power_in"))
      (node (ref "LED5") (pin "3-GND") (pinfunction "GND_3-GND") (pintype "power_in"))
      (node (ref "LED6") (pin "3-GND") (pinfunction "GND_3-GND") (pintype "power_in"))
      (node (ref "LED7") (pin "3-GND") (pinfunction "GND_3-GND") (pintype "power_in"))
      (node (ref "LED8") (pin "3-GND") (pinfunction "GND_3-GND") (pintype "power_in"))
      (node (ref "LED9") (pin "3-GND") (pinfunction "GND_3-GND") (pintype "power_in"))
      (node (ref "Q8") (pin "2") (pinfunction "GND_2") (pintype "passive"))
    )
    (net (code "6") (name "Net-(LED-DO)") (class "Default")
      (node (ref "LED") (pin "2-DOUT") (pinfunction "DO_2-DOUT") (pintype "output"))
      (node (ref "LED5") (pin "4-DIN") (pinfunction "DI_4-DIN") (pintype "input"))
    )
    (net (code "7") (name "Net-(LED5-DO)") (class "Default")
      (node (ref "LED5") (pin "2-DOUT") (pinfunction "DO_2-DOUT") (pintype "output"))
      (node (ref "LED6") (pin "4-DIN") (pinfunction "DI_4-DIN") (pintype "input"))
    )
    (net (code "8") (name "Net-(LED6-DO)") (class "Default")
      (node (ref "LED6") (pin "2-DOUT") (pinfunction "DO_2-DOUT") (pintype "output"))
      (node (ref "LED7") (pin "4-DIN") (pinfunction "DI_4-DIN") (pintype "input"))
    )
    (net (code "9") (name "Net-(LED7-DO)") (class "Default")
      (node (ref "LED7") (pin "2-DOUT") (pinfunction "DO_2-DOUT") (pintype "output"))
      (node (ref "LED8") (pin "4-DIN") (pinfunction "DI_4-DIN") (pintype "input"))
    )
    (net (code "10") (name "Net-(LED8-DO)") (class "Default")
      (node (ref "LED8") (pin "2-DOUT") (pinfunction "DO_2-DOUT") (pintype "output"))
      (node (ref "LED9") (pin "4-DIN") (pinfunction "DI_4-DIN") (pintype "input"))
    )
    (net (code "11") (name "Net-(LED10-DI)") (class "Default")
      (node (ref "LED10") (pin "4-DIN") (pinfunction "DI_4-DIN") (pintype "input"))
      (node (ref "LED9") (pin "2-DOUT") (pinfunction "DO_2-DOUT") (pintype "output"))
    )
    (net (code "12") (name "Net-(LED10-DO)") (class "Default")
      (node (ref "LED10") (pin "2-DOUT") (pinfunction "DO_2-DOUT") (pintype "output"))
      (node (ref "LED11") (pin "4-DIN") (pinfunction "DI_4-DIN") (pintype "input"))
    )
    (net (code "13") (name "Net-(LED11-DO)") (class "Default")
      (node (ref "LED11") (pin "2-DOUT") (pinfunction "DO_2-DOUT") (pintype "output"))
      (node (ref "LED19") (pin "4-DIN") (pinfunction "DI_4-DIN") (pintype "input"))
    )
    (net (code "14") (name "Net-(LED12-DI)") (class "Default")
      (node (ref "LED12") (pin "4-DIN") (pinfunction "DI_4-DIN") (pintype "input"))
      (node (ref "LED13") (pin "2-DOUT") (pinfunction "DO_2-DOUT") (pintype "output"))
    )
    (net (code "15") (name "Net-(LED12-DO)") (class "Default")
      (node (ref "LED12") (pin "2-DOUT") (pinfunction "DO_2-DOUT") (pintype "output"))
      (node (ref "LED20") (pin "4-DIN") (pinfunction "DI_4-DIN") (pintype "input"))
    )
    (net (code "16") (name "Net-(LED13-DI)") (class "Default")
      (node (ref "LED13") (pin "4-DIN") (pinfunction "DI_4-DIN") (pintype "input"))
      (node (ref "LED14") (pin "2-DOUT") (pinfunction "DO_2-DOUT") (pintype "output"))
    )
    (net (code "17") (name "Net-(LED14-DI)") (class "Default")
      (node (ref "LED14") (pin "4-DIN") (pinfunction "DI_4-DIN") (pintype "input"))
      (node (ref "LED15") (pin "2-DOUT") (pinfunction "DO_2-DOUT") (pintype "output"))
    )
    (net (code "18") (name "Net-(LED15-DI)") (class "Default")
      (node (ref "LED15") (pin "4-DIN") (pinfunction "DI_4-DIN") (pintype "input"))
      (node (ref "LED16") (pin "2-DOUT") (pinfunction "DO_2-DOUT") (pintype "output"))
    )
    (net (code "19") (name "Net-(LED16-DI)") (class "Default")
      (node (ref "LED16") (pin "4-DIN") (pinfunction "DI_4-DIN") (pintype "input"))
      (node (ref "LED17") (pin "2-DOUT") (pinfunction "DO_2-DOUT") (pintype "output"))
    )
    (net (code "20") (name "Net-(LED17-DI)") (class "Default")
      (node (ref "LED17") (pin "4-DIN") (pinfunction "DI_4-DIN") (pintype "input"))
      (node (ref "LED18") (pin "2-DOUT") (pinfunction "DO_2-DOUT") (pintype "output"))
    )
    (net (code "21") (name "Net-(LED18-DI)") (class "Default")
      (node (ref "LED18") (pin "4-DIN") (pinfunction "DI_4-DIN") (pintype "input"))
      (node (ref "LED19") (pin "2-DOUT") (pinfunction "DO_2-DOUT") (pintype "output"))
    )
    (net (code "22") (name "Net-(LED20-DO)") (class "Default")
      (node (ref "LED20") (pin "2-DOUT") (pinfunction "DO_2-DOUT") (pintype "output"))
      (node (ref "LED21") (pin "4-DIN") (pinfunction "DI_4-DIN") (pintype "input"))
    )
    (net (code "23") (name "Net-(LED21-DO)") (class "Default")
      (node (ref "LED21") (pin "2-DOUT") (pinfunction "DO_2-DOUT") (pintype "output"))
      (node (ref "LED22") (pin "4-DIN") (pinfunction "DI_4-DIN") (pintype "input"))
    )
    (net (code "24") (name "Net-(LED22-DO)") (class "Default")
      (node (ref "LED22") (pin "2-DOUT") (pinfunction "DO_2-DOUT") (pintype "output"))
      (node (ref "LED23") (pin "4-DIN") (pinfunction "DI_4-DIN") (pintype "input"))
    )
    (net (code "25") (name "Net-(LED23-DO)") (class "Default")
      (node (ref "LED23") (pin "2-DOUT") (pinfunction "DO_2-DOUT") (pintype "output"))
      (node (ref "LED24") (pin "4-DIN") (pinfunction "DI_4-DIN") (pintype "input"))
    )
    (net (code "26") (name "Net-(LED24-DO)") (class "Default")
      (node (ref "LED24") (pin "2-DOUT") (pinfunction "DO_2-DOUT") (pintype "output"))
      (node (ref "LED25") (pin "4-DIN") (pinfunction "DI_4-DIN") (pintype "input"))
    )
    (net (code "27") (name "Net-(LED25-DO)") (class "Default")
      (node (ref "LED25") (pin "2-DOUT") (pinfunction "DO_2-DOUT") (pintype "output"))
      (node (ref "LED26") (pin "4-DIN") (pinfunction "DI_4-DIN") (pintype "input"))
    )
    (net (code "28") (name "Net-(LED26-DO)") (class "Default")
      (node (ref "LED26") (pin "2-DOUT") (pinfunction "DO_2-DOUT") (pintype "output"))
      (node (ref "LED27") (pin "4-DIN") (pinfunction "DI_4-DIN") (pintype "input"))
    )
    (net (code "29") (name "Net-(LED27-DO)") (class "Default")
      (node (ref "LED27") (pin "2-DOUT") (pinfunction "DO_2-DOUT") (pintype "output"))
      (node (ref "LED34") (pin "4-DIN") (pinfunction "DI_4-DIN") (pintype "input"))
    )
    (net (code "30") (name "Net-(LED28-DI)") (class "Default")
      (node (ref "LED28") (pin "4-DIN") (pinfunction "DI_4-DIN") (pintype "input"))
      (node (ref "LED29") (pin "2-DOUT") (pinfunction "DO_2-DOUT") (pintype "output"))
    )
    (net (code "31") (name "Net-(LED28-DO)") (class "Default")
      (node (ref "LED28") (pin "2-DOUT") (pinfunction "DO_2-DOUT") (pintype "output"))
      (node (ref "LED35") (pin "4-DIN") (pinfunction "DI_4-DIN") (pintype "input"))
    )
    (net (code "32") (name "Net-(LED29-DI)") (class "Default")
      (node (ref "LED29") (pin "4-DIN") (pinfunction "DI_4-DIN") (pintype "input"))
      (node (ref "LED30") (pin "2-DOUT") (pinfunction "DO_2-DOUT") (pintype "output"))
    )
    (net (code "33") (name "Net-(LED30-DI)") (class "Default")
      (node (ref "LED30") (pin "4-DIN") (pinfunction "DI_4-DIN") (pintype "input"))
      (node (ref "LED31") (pin "2-DOUT") (pinfunction "DO_2-DOUT") (pintype "output"))
    )
    (net (code "34") (name "Net-(LED31-DI)") (class "Default")
      (node (ref "LED31") (pin "4-DIN") (pinfunction "DI_4-DIN") (pintype "input"))
      (node (ref "LED32") (pin "2-DOUT") (pinfunction "DO_2-DOUT") (pintype "output"))
    )
    (net (code "35") (name "Net-(LED32-DI)") (class "Default")
      (node (ref "LED32") (pin "4-DIN") (pinfunction "DI_4-DIN") (pintype "input"))
      (node (ref "LED33") (pin "2-DOUT") (pinfunction "DO_2-DOUT") (pintype "output"))
    )
    (net (code "36") (name "Net-(LED33-DI)") (class "Default")
      (node (ref "LED33") (pin "4-DIN") (pinfunction "DI_4-DIN") (pintype "input"))
      (node (ref "LED34") (pin "2-DOUT") (pinfunction "DO_2-DOUT") (pintype "output"))
    )
    (net (code "37") (name "Net-(LED35-DO)") (class "Default")
      (node (ref "LED35") (pin "2-DOUT") (pinfunction "DO_2-DOUT") (pintype "output"))
      (node (ref "LED36") (pin "4-DIN") (pinfunction "DI_4-DIN") (pintype "input"))
    )
    (net (code "38") (name "Net-(LED36-DO)") (class "Default")
      (node (ref "LED36") (pin "2-DOUT") (pinfunction "DO_2-DOUT") (pintype "output"))
      (node (ref "LED37") (pin "4-DIN") (pinfunction "DI_4-DIN") (pintype "input"))
    )
    (net (code "39") (name "Net-(LED37-DO)") (class "Default")
      (node (ref "LED37") (pin "2-DOUT") (pinfunction "DO_2-DOUT") (pintype "output"))
      (node (ref "LED38") (pin "4-DIN") (pinfunction "DI_4-DIN") (pintype "input"))
    )
    (net (code "40") (name "Net-(LED38-DO)") (class "Default")
      (node (ref "LED38") (pin "2-DOUT") (pinfunction "DO_2-DOUT") (pintype "output"))
      (node (ref "LED39") (pin "4-DIN") (pinfunction "DI_4-DIN") (pintype "input"))
    )
    (net (code "41") (name "Net-(LED39-DO)") (class "Default")
      (node (ref "LED39") (pin "2-DOUT") (pinfunction "DO_2-DOUT") (pintype "output"))
      (node (ref "LED40") (pin "4-DIN") (pinfunction "DI_4-DIN") (pintype "input"))
    )
    (net (code "42") (name "Net-(LED40-DO)") (class "Default")
      (node (ref "LED40") (pin "2-DOUT") (pinfunction "DO_2-DOUT") (pintype "output"))
      (node (ref "LED41") (pin "4-DIN") (pinfunction "DI_4-DIN") (pintype "input"))
    )
    (net (code "43") (name "Net-(Q8-ON)") (class "Default")
      (node (ref "Q8") (pin "3") (pinfunction "ON_3") (pintype "bidirectional"))
      (node (ref "R37") (pin "1") (pinfunction "1_1") (pintype "passive"))
    )
    (net (code "44") (name "VMCU") (class "Default")
      (node (ref "C29") (pin "1") (pinfunction "1_1") (pintype "passive"))
      (node (ref "Q8") (pin "1") (pinfunction "IN_1") (pintype "input"))
    )
    (net (code "45") (name "unconnected-(LED41-DO-Pad2-DOUT)") (class "Default")
      (node (ref "LED41") (pin "2-DOUT") (pinfunction "DO_2-DOUT") (pintype "output+no_connect"))
    )
    (net (code "46") (name "unconnected-(Q8-QOD-Pad5)") (class "Default")
      (node (ref "Q8") (pin "5") (pinfunction "QOD_5") (pintype "output+no_connect"))
    )
  )
)
